# video_and_power.net
KiCad netlist of a schematic drawn in EAGLE
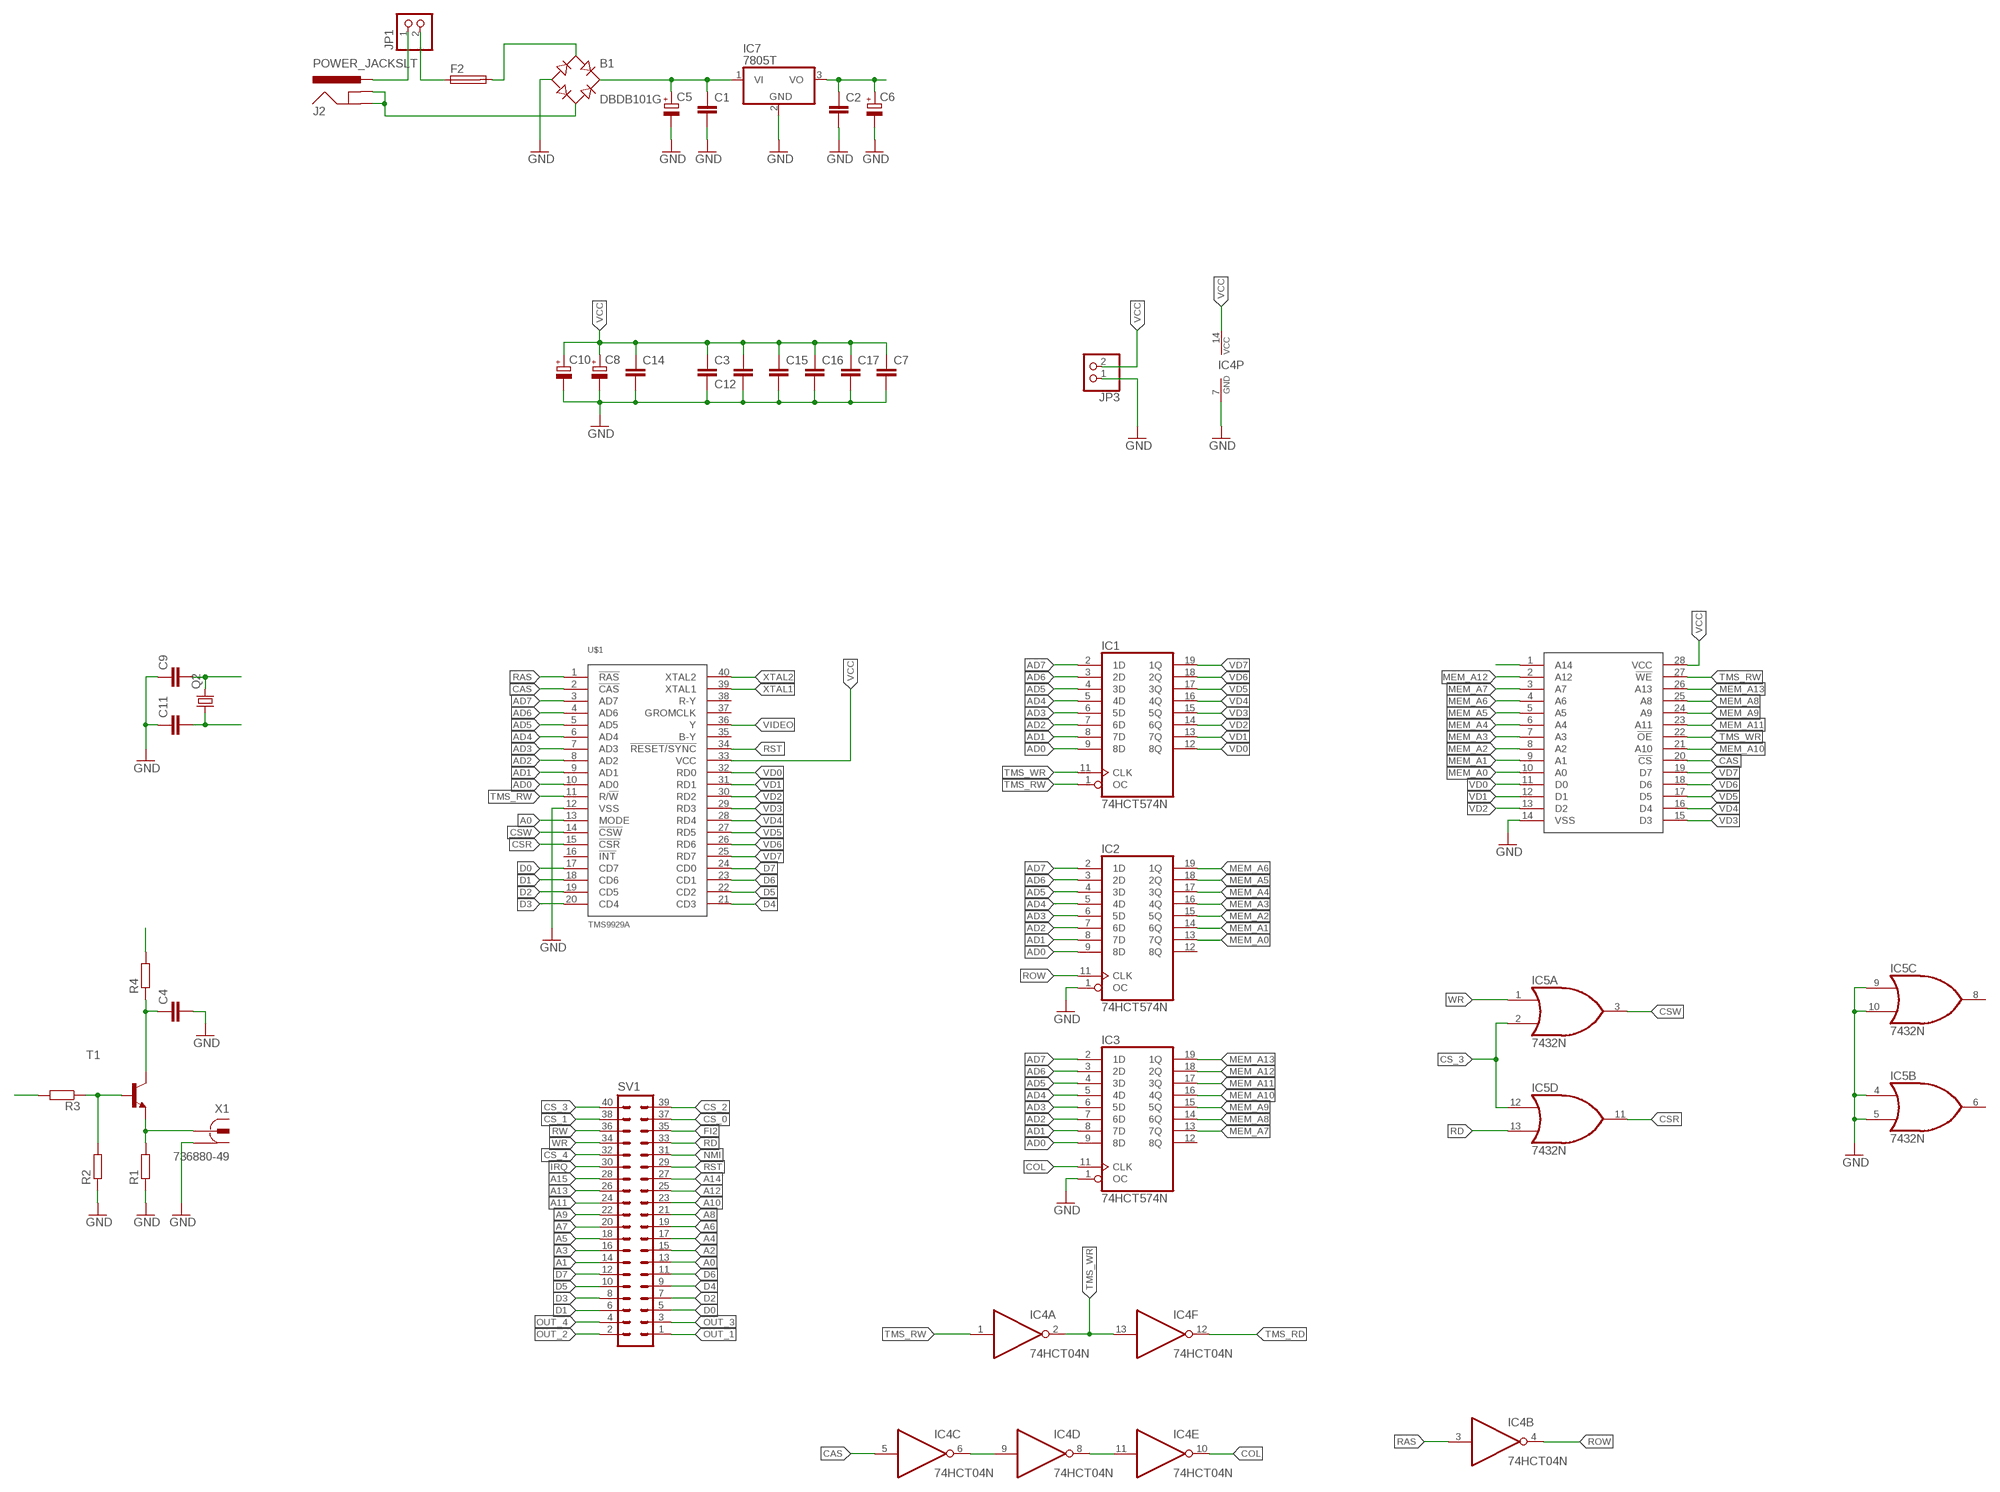
[diagram p0: schematic, sheet 1]

(export (version "E")
  (design (tool "Eeschema 10.0.6"))
  (components
    (comp (ref "B1")
      (value "DBDB101G")
      (footprint "eagle-import:DB")
      (libsource (lib "eagle-import") (part "DB?GDB101"))
    )
    (comp (ref "C1")
      (value "C-EUC1206")
      (footprint "eagle-import:C1206")
      (libsource (lib "eagle-import") (part "C-EUC1206"))
    )
    (comp (ref "C2")
      (value "C-EUC1206")
      (footprint "eagle-import:C1206")
      (libsource (lib "eagle-import") (part "C-EUC1206"))
    )
    (comp (ref "C3")
      (value "C-EUC0603")
      (footprint "eagle-import:C0603")
      (libsource (lib "eagle-import") (part "C-EUC0603"))
    )
    (comp (ref "C4")
      (value "C-EUC0603")
      (footprint "eagle-import:C0603")
      (libsource (lib "eagle-import") (part "C-EUC0603"))
    )
    (comp (ref "C5")
      (value "CPOL-EUE5-10.5")
      (footprint "eagle-import:E5-10,5")
      (libsource (lib "eagle-import") (part "CPOL-EUE5-10.5"))
    )
    (comp (ref "C6")
      (value "CPOL-EUE5-10.5")
      (footprint "eagle-import:E5-10,5")
      (libsource (lib "eagle-import") (part "CPOL-EUE5-10.5"))
    )
    (comp (ref "C7")
      (value "C-EUC1206")
      (footprint "eagle-import:C1206")
      (libsource (lib "eagle-import") (part "C-EUC1206"))
    )
    (comp (ref "C8")
      (value "CPOL-EUE5-10.5")
      (footprint "eagle-import:E5-10,5")
      (libsource (lib "eagle-import") (part "CPOL-EUE5-10.5"))
    )
    (comp (ref "C9")
      (value "C-EUC0603")
      (footprint "eagle-import:C0603")
      (libsource (lib "eagle-import") (part "C-EUC0603"))
    )
    (comp (ref "C10")
      (value "CPOL-EUE5-10.5")
      (footprint "eagle-import:E5-10,5")
      (libsource (lib "eagle-import") (part "CPOL-EUE5-10.5"))
    )
    (comp (ref "C11")
      (value "C-EUC0603")
      (footprint "eagle-import:C0603")
      (libsource (lib "eagle-import") (part "C-EUC0603"))
    )
    (comp (ref "C12")
      (value "C-EUC0603")
      (footprint "eagle-import:C0603")
      (libsource (lib "eagle-import") (part "C-EUC0603"))
    )
    (comp (ref "C14")
      (value "C-EUC1206")
      (footprint "eagle-import:C1206")
      (libsource (lib "eagle-import") (part "C-EUC1206"))
    )
    (comp (ref "C15")
      (value "C-EUC1206")
      (footprint "eagle-import:C1206")
      (libsource (lib "eagle-import") (part "C-EUC1206"))
    )
    (comp (ref "C16")
      (value "C-EUC0603")
      (footprint "eagle-import:C0603")
      (libsource (lib "eagle-import") (part "C-EUC0603"))
    )
    (comp (ref "C17")
      (value "C-EUC0603")
      (footprint "eagle-import:C0603")
      (libsource (lib "eagle-import") (part "C-EUC0603"))
    )
    (comp (ref "F2")
      (value "SH22,5")
      (footprint "eagle-import:SH22,5")
      (fields
        (field (name "MF") "SCHURTER")
        (field (name "MPN") "0031.8201")
        (field (name "MF_1") "SCHURTER")
        (field (name "MPN_1") "0031.8201")
        (field (name "OC_FARNELL") "1162740")
        (field (name "OC_NEWARK") "96F8317")
      )
      (libsource (lib "eagle-import") (part "SH22,5"))
    )
    (comp (ref "IC1")
      (value "74HCT574N")
      (footprint "eagle-import:DIL20")
      (libsource (lib "eagle-import") (part "74574NHCT"))
    )
    (comp (ref "IC2")
      (value "74HCT574N")
      (footprint "eagle-import:DIL20")
      (libsource (lib "eagle-import") (part "74574NHCT"))
    )
    (comp (ref "IC3")
      (value "74HCT574N")
      (footprint "eagle-import:DIL20")
      (libsource (lib "eagle-import") (part "74574NHCT"))
    )
    (comp (ref "IC4")
      (value "74HCT04N")
      (footprint "eagle-import:DIL14")
      (libsource (lib "eagle-import") (part "7404NHCT"))
    )
    (comp (ref "IC5")
      (value "7432N")
      (footprint "eagle-import:DIL14")
      (libsource (lib "eagle-import") (part "7432N"))
    )
    (comp (ref "IC7")
      (value "7805T")
      (footprint "eagle-import:TO220H")
      (libsource (lib "eagle-import") (part "78T05"))
    )
    (comp (ref "J2")
      (value "POWER_JACKSLT")
      (footprint "eagle-import:POWER_JACK_SLOT")
      (libsource (lib "eagle-import") (part "POWER_JACKSLT"))
    )
    (comp (ref "JP1")
      (value "PINHD-1X2")
      (footprint "eagle-import:1X02")
      (libsource (lib "eagle-import") (part "PINHD-1X2"))
    )
    (comp (ref "JP3")
      (value "PINHD-1X2/90")
      (footprint "eagle-import:1X02_90")
      (libsource (lib "eagle-import") (part "PINHD-1X2/90"))
    )
    (comp (ref "Q2")
      (value "CRYSTALHC49S")
      (footprint "eagle-import:HC49_S")
      (libsource (lib "eagle-import") (part "CRYSTALHC49S"))
    )
    (comp (ref "R1")
      (value "R-EU_R0603")
      (footprint "eagle-import:R0603")
      (libsource (lib "eagle-import") (part "R-EU_R0603"))
    )
    (comp (ref "R2")
      (value "R-EU_R0603")
      (footprint "eagle-import:R0603")
      (libsource (lib "eagle-import") (part "R-EU_R0603"))
    )
    (comp (ref "R3")
      (value "R-EU_0204/7")
      (footprint "eagle-import:0204_7")
      (libsource (lib "eagle-import") (part "R-EU_0204/7"))
    )
    (comp (ref "R4")
      (value "R-EU_R0805")
      (footprint "eagle-import:R0805")
      (libsource (lib "eagle-import") (part "R-EU_R0805"))
    )
    (comp (ref "SV1")
      (value "ML40L")
      (footprint "eagle-import:ML40L")
      (libsource (lib "eagle-import") (part "ML40L"))
    )
    (comp (ref "T1")
      (value "2N4401-NPN-TO92-EBC")
      (footprint "eagle-import:TO92-EBC")
      (libsource (lib "eagle-import") (part "-NPN-TO92-EBC2N4401"))
    )
    (comp (ref "U$1")
      (value "TMS9929A")
      (footprint "eagle-import:DIL40")
      (libsource (lib "eagle-import") (part "TMS9929A"))
    )
    (comp (ref "U$2")
      (value "62256")
      (footprint "eagle-import:DIL28-6")
      (libsource (lib "eagle-import") (part "62256"))
    )
    (comp (ref "X1")
      (value "736880-49")
      (footprint "eagle-import:736880-49")
      (libsource (lib "eagle-import") (part "736880-49"))
    )
  )
  (nets
    (net (code "1") (name "A0") (class "Default")
      (node (ref "SV1") (pin "13") (pinfunction "13_13") (pintype "passive"))
      (node (ref "U$1") (pin "13") (pinfunction "MODE_13") (pintype "bidirectional"))
    )
    (net (code "2") (name "A1") (class "Default")
      (node (ref "SV1") (pin "14") (pinfunction "14_14") (pintype "passive"))
    )
    (net (code "3") (name "A2") (class "Default")
      (node (ref "SV1") (pin "15") (pinfunction "15_15") (pintype "passive"))
    )
    (net (code "4") (name "A3") (class "Default")
      (node (ref "SV1") (pin "16") (pinfunction "16_16") (pintype "passive"))
    )
    (net (code "5") (name "A4") (class "Default")
      (node (ref "SV1") (pin "17") (pinfunction "17_17") (pintype "passive"))
    )
    (net (code "6") (name "A5") (class "Default")
      (node (ref "SV1") (pin "18") (pinfunction "18_18") (pintype "passive"))
    )
    (net (code "7") (name "A6") (class "Default")
      (node (ref "SV1") (pin "19") (pinfunction "19_19") (pintype "passive"))
    )
    (net (code "8") (name "A7") (class "Default")
      (node (ref "SV1") (pin "20") (pinfunction "20_20") (pintype "passive"))
    )
    (net (code "9") (name "A8") (class "Default")
      (node (ref "SV1") (pin "21") (pinfunction "21_21") (pintype "passive"))
    )
    (net (code "10") (name "A9") (class "Default")
      (node (ref "SV1") (pin "22") (pinfunction "22_22") (pintype "passive"))
    )
    (net (code "11") (name "A10") (class "Default")
      (node (ref "SV1") (pin "23") (pinfunction "23_23") (pintype "passive"))
    )
    (net (code "12") (name "A11") (class "Default")
      (node (ref "SV1") (pin "24") (pinfunction "24_24") (pintype "passive"))
    )
    (net (code "13") (name "A12") (class "Default")
      (node (ref "SV1") (pin "25") (pinfunction "25_25") (pintype "passive"))
    )
    (net (code "14") (name "A13") (class "Default")
      (node (ref "SV1") (pin "26") (pinfunction "26_26") (pintype "passive"))
    )
    (net (code "15") (name "A14") (class "Default")
      (node (ref "SV1") (pin "27") (pinfunction "27_27") (pintype "passive"))
    )
    (net (code "16") (name "A15") (class "Default")
      (node (ref "SV1") (pin "28") (pinfunction "28_28") (pintype "passive"))
    )
    (net (code "17") (name "AD0") (class "Default")
      (node (ref "IC1") (pin "9") (pinfunction "8D_9") (pintype "input"))
      (node (ref "IC2") (pin "9") (pinfunction "8D_9") (pintype "input"))
      (node (ref "IC3") (pin "9") (pinfunction "8D_9") (pintype "input"))
      (node (ref "U$1") (pin "10") (pinfunction "AD0_10") (pintype "bidirectional"))
    )
    (net (code "18") (name "AD1") (class "Default")
      (node (ref "IC1") (pin "8") (pinfunction "7D_8") (pintype "input"))
      (node (ref "IC2") (pin "8") (pinfunction "7D_8") (pintype "input"))
      (node (ref "IC3") (pin "8") (pinfunction "7D_8") (pintype "input"))
      (node (ref "U$1") (pin "9") (pinfunction "AD1_9") (pintype "bidirectional"))
    )
    (net (code "19") (name "AD2") (class "Default")
      (node (ref "IC1") (pin "7") (pinfunction "6D_7") (pintype "input"))
      (node (ref "IC2") (pin "7") (pinfunction "6D_7") (pintype "input"))
      (node (ref "IC3") (pin "7") (pinfunction "6D_7") (pintype "input"))
      (node (ref "U$1") (pin "8") (pinfunction "AD2_8") (pintype "bidirectional"))
    )
    (net (code "20") (name "AD3") (class "Default")
      (node (ref "IC1") (pin "6") (pinfunction "5D_6") (pintype "input"))
      (node (ref "IC2") (pin "6") (pinfunction "5D_6") (pintype "input"))
      (node (ref "IC3") (pin "6") (pinfunction "5D_6") (pintype "input"))
      (node (ref "U$1") (pin "7") (pinfunction "AD3_7") (pintype "bidirectional"))
    )
    (net (code "21") (name "AD4") (class "Default")
      (node (ref "IC1") (pin "5") (pinfunction "4D_5") (pintype "input"))
      (node (ref "IC2") (pin "5") (pinfunction "4D_5") (pintype "input"))
      (node (ref "IC3") (pin "5") (pinfunction "4D_5") (pintype "input"))
      (node (ref "U$1") (pin "6") (pinfunction "AD4_6") (pintype "bidirectional"))
    )
    (net (code "22") (name "AD5") (class "Default")
      (node (ref "IC1") (pin "4") (pinfunction "3D_4") (pintype "input"))
      (node (ref "IC2") (pin "4") (pinfunction "3D_4") (pintype "input"))
      (node (ref "IC3") (pin "4") (pinfunction "3D_4") (pintype "input"))
      (node (ref "U$1") (pin "5") (pinfunction "AD5_5") (pintype "bidirectional"))
    )
    (net (code "23") (name "AD6") (class "Default")
      (node (ref "IC1") (pin "3") (pinfunction "2D_3") (pintype "input"))
      (node (ref "IC2") (pin "3") (pinfunction "2D_3") (pintype "input"))
      (node (ref "IC3") (pin "3") (pinfunction "2D_3") (pintype "input"))
      (node (ref "U$1") (pin "4") (pinfunction "AD6_4") (pintype "bidirectional"))
    )
    (net (code "24") (name "AD7") (class "Default")
      (node (ref "IC1") (pin "2") (pinfunction "1D_2") (pintype "input"))
      (node (ref "IC2") (pin "2") (pinfunction "1D_2") (pintype "input"))
      (node (ref "IC3") (pin "2") (pinfunction "1D_2") (pintype "input"))
      (node (ref "U$1") (pin "3") (pinfunction "AD7_3") (pintype "bidirectional"))
    )
    (net (code "25") (name "CAS") (class "Default")
      (node (ref "IC4") (pin "5") (pinfunction "I_5") (pintype "input"))
      (node (ref "U$1") (pin "2") (pinfunction "~{CAS}_2") (pintype "bidirectional"))
      (node (ref "U$2") (pin "20") (pinfunction "~{CS}_20") (pintype "bidirectional"))
    )
    (net (code "26") (name "COL") (class "Default")
      (node (ref "IC3") (pin "11") (pinfunction "CLK_11") (pintype "input"))
      (node (ref "IC4") (pin "10") (pinfunction "O_10") (pintype "output"))
    )
    (net (code "27") (name "CSR") (class "Default")
      (node (ref "IC5") (pin "11") (pinfunction "O_11") (pintype "output"))
      (node (ref "U$1") (pin "15") (pinfunction "~{CSR}_15") (pintype "bidirectional"))
    )
    (net (code "28") (name "CSW") (class "Default")
      (node (ref "IC5") (pin "3") (pinfunction "O_3") (pintype "output"))
      (node (ref "U$1") (pin "14") (pinfunction "~{CSW}_14") (pintype "bidirectional"))
    )
    (net (code "29") (name "CS_0") (class "Default")
      (node (ref "SV1") (pin "37") (pinfunction "37_37") (pintype "passive"))
    )
    (net (code "30") (name "CS_1") (class "Default")
      (node (ref "SV1") (pin "38") (pinfunction "38_38") (pintype "passive"))
    )
    (net (code "31") (name "CS_2") (class "Default")
      (node (ref "SV1") (pin "39") (pinfunction "39_39") (pintype "passive"))
    )
    (net (code "32") (name "CS_3") (class "Default")
      (node (ref "IC5") (pin "12") (pinfunction "I0_12") (pintype "input"))
      (node (ref "IC5") (pin "2") (pinfunction "I1_2") (pintype "input"))
      (node (ref "SV1") (pin "40") (pinfunction "40_40") (pintype "passive"))
    )
    (net (code "33") (name "CS_4") (class "Default")
      (node (ref "SV1") (pin "32") (pinfunction "32_32") (pintype "passive"))
    )
    (net (code "34") (name "D0") (class "Default")
      (node (ref "SV1") (pin "5") (pinfunction "5_5") (pintype "passive"))
      (node (ref "U$1") (pin "17") (pinfunction "CD7_17") (pintype "bidirectional"))
    )
    (net (code "35") (name "D1") (class "Default")
      (node (ref "SV1") (pin "6") (pinfunction "6_6") (pintype "passive"))
      (node (ref "U$1") (pin "18") (pinfunction "CD6_18") (pintype "bidirectional"))
    )
    (net (code "36") (name "D2") (class "Default")
      (node (ref "SV1") (pin "7") (pinfunction "7_7") (pintype "passive"))
      (node (ref "U$1") (pin "19") (pinfunction "CD5_19") (pintype "bidirectional"))
    )
    (net (code "37") (name "D3") (class "Default")
      (node (ref "SV1") (pin "8") (pinfunction "8_8") (pintype "passive"))
      (node (ref "U$1") (pin "20") (pinfunction "CD4_20") (pintype "bidirectional"))
    )
    (net (code "38") (name "D4") (class "Default")
      (node (ref "SV1") (pin "9") (pinfunction "9_9") (pintype "passive"))
      (node (ref "U$1") (pin "21") (pinfunction "CD3_21") (pintype "bidirectional"))
    )
    (net (code "39") (name "D5") (class "Default")
      (node (ref "SV1") (pin "10") (pinfunction "10_10") (pintype "passive"))
      (node (ref "U$1") (pin "22") (pinfunction "CD2_22") (pintype "bidirectional"))
    )
    (net (code "40") (name "D6") (class "Default")
      (node (ref "SV1") (pin "11") (pinfunction "11_11") (pintype "passive"))
      (node (ref "U$1") (pin "23") (pinfunction "CD1_23") (pintype "bidirectional"))
    )
    (net (code "41") (name "D7") (class "Default")
      (node (ref "SV1") (pin "12") (pinfunction "12_12") (pintype "passive"))
      (node (ref "U$1") (pin "24") (pinfunction "CD0_24") (pintype "bidirectional"))
    )
    (net (code "42") (name "FI2") (class "Default")
      (node (ref "SV1") (pin "35") (pinfunction "35_35") (pintype "passive"))
    )
    (net (code "43") (name "GND") (class "Default")
      (node (ref "B1") (pin "-") (pinfunction "-_-") (pintype "passive"))
      (node (ref "C1") (pin "2") (pinfunction "2_2") (pintype "passive"))
      (node (ref "C10") (pin "-") (pinfunction "-_-") (pintype "passive"))
      (node (ref "C11") (pin "1") (pinfunction "1_1") (pintype "passive"))
      (node (ref "C12") (pin "1") (pinfunction "1_1") (pintype "passive"))
      (node (ref "C14") (pin "2") (pinfunction "2_2") (pintype "passive"))
      (node (ref "C15") (pin "2") (pinfunction "2_2") (pintype "passive"))
      (node (ref "C16") (pin "2") (pinfunction "2_2") (pintype "passive"))
      (node (ref "C17") (pin "2") (pinfunction "2_2") (pintype "passive"))
      (node (ref "C2") (pin "2") (pinfunction "2_2") (pintype "passive"))
      (node (ref "C3") (pin "2") (pinfunction "2_2") (pintype "passive"))
      (node (ref "C4") (pin "2") (pinfunction "2_2") (pintype "passive"))
      (node (ref "C5") (pin "-") (pinfunction "-_-") (pintype "passive"))
      (node (ref "C6") (pin "-") (pinfunction "-_-") (pintype "passive"))
      (node (ref "C7") (pin "2") (pinfunction "2_2") (pintype "passive"))
      (node (ref "C8") (pin "-") (pinfunction "-_-") (pintype "passive"))
      (node (ref "C9") (pin "1") (pinfunction "1_1") (pintype "passive"))
      (node (ref "IC2") (pin "1") (pinfunction "OC_1") (pintype "input"))
      (node (ref "IC3") (pin "1") (pinfunction "OC_1") (pintype "input"))
      (node (ref "IC4") (pin "7") (pinfunction "GND_7") (pintype "power_in"))
      (node (ref "IC5") (pin "10") (pinfunction "I1_10") (pintype "input"))
      (node (ref "IC5") (pin "4") (pinfunction "I0_4") (pintype "input"))
      (node (ref "IC5") (pin "5") (pinfunction "I1_5") (pintype "input"))
      (node (ref "IC5") (pin "9") (pinfunction "I0_9") (pintype "input"))
      (node (ref "IC7") (pin "2") (pinfunction "GND_2") (pintype "passive"))
      (node (ref "JP3") (pin "1") (pinfunction "1_1") (pintype "passive"))
      (node (ref "R1") (pin "1") (pinfunction "1_1") (pintype "passive"))
      (node (ref "R2") (pin "1") (pinfunction "1_1") (pintype "passive"))
      (node (ref "U$1") (pin "12") (pinfunction "VSS_12") (pintype "bidirectional"))
      (node (ref "U$2") (pin "14") (pinfunction "VSS_14") (pintype "bidirectional"))
      (node (ref "X1") (pin "1") (pinfunction "1_1") (pintype "passive"))
      (node (ref "X1") (pin "1@1") (pinfunction "1_1@1") (pintype "passive"))
      (node (ref "X1") (pin "1@2") (pinfunction "1_1@2") (pintype "passive"))
    )
    (net (code "44") (name "IRQ") (class "Default")
      (node (ref "SV1") (pin "30") (pinfunction "30_30") (pintype "passive"))
    )
    (net (code "45") (name "MEM_A0") (class "Default")
      (node (ref "IC2") (pin "13") (pinfunction "7Q_13") (pintype "tri_state"))
      (node (ref "U$2") (pin "10") (pinfunction "A0_10") (pintype "bidirectional"))
    )
    (net (code "46") (name "MEM_A1") (class "Default")
      (node (ref "IC2") (pin "14") (pinfunction "6Q_14") (pintype "tri_state"))
      (node (ref "U$2") (pin "9") (pinfunction "A1_9") (pintype "bidirectional"))
    )
    (net (code "47") (name "MEM_A2") (class "Default")
      (node (ref "IC2") (pin "15") (pinfunction "5Q_15") (pintype "tri_state"))
      (node (ref "U$2") (pin "8") (pinfunction "A2_8") (pintype "bidirectional"))
    )
    (net (code "48") (name "MEM_A3") (class "Default")
      (node (ref "IC2") (pin "16") (pinfunction "4Q_16") (pintype "tri_state"))
      (node (ref "U$2") (pin "7") (pinfunction "A3_7") (pintype "bidirectional"))
    )
    (net (code "49") (name "MEM_A4") (class "Default")
      (node (ref "IC2") (pin "17") (pinfunction "3Q_17") (pintype "tri_state"))
      (node (ref "U$2") (pin "6") (pinfunction "A4_6") (pintype "bidirectional"))
    )
    (net (code "50") (name "MEM_A5") (class "Default")
      (node (ref "IC2") (pin "18") (pinfunction "2Q_18") (pintype "tri_state"))
      (node (ref "U$2") (pin "5") (pinfunction "A5_5") (pintype "bidirectional"))
    )
    (net (code "51") (name "MEM_A6") (class "Default")
      (node (ref "IC2") (pin "19") (pinfunction "1Q_19") (pintype "tri_state"))
      (node (ref "U$2") (pin "4") (pinfunction "A6_4") (pintype "bidirectional"))
    )
    (net (code "52") (name "MEM_A7") (class "Default")
      (node (ref "IC3") (pin "13") (pinfunction "7Q_13") (pintype "tri_state"))
      (node (ref "U$2") (pin "3") (pinfunction "A7_3") (pintype "bidirectional"))
    )
    (net (code "53") (name "MEM_A8") (class "Default")
      (node (ref "IC3") (pin "14") (pinfunction "6Q_14") (pintype "tri_state"))
      (node (ref "U$2") (pin "25") (pinfunction "A8_25") (pintype "bidirectional"))
    )
    (net (code "54") (name "MEM_A9") (class "Default")
      (node (ref "IC3") (pin "15") (pinfunction "5Q_15") (pintype "tri_state"))
      (node (ref "U$2") (pin "24") (pinfunction "A9_24") (pintype "bidirectional"))
    )
    (net (code "55") (name "MEM_A10") (class "Default")
      (node (ref "IC3") (pin "16") (pinfunction "4Q_16") (pintype "tri_state"))
      (node (ref "U$2") (pin "21") (pinfunction "A10_21") (pintype "bidirectional"))
    )
    (net (code "56") (name "MEM_A11") (class "Default")
      (node (ref "IC3") (pin "17") (pinfunction "3Q_17") (pintype "tri_state"))
      (node (ref "U$2") (pin "23") (pinfunction "A11_23") (pintype "bidirectional"))
    )
    (net (code "57") (name "MEM_A12") (class "Default")
      (node (ref "IC3") (pin "18") (pinfunction "2Q_18") (pintype "tri_state"))
      (node (ref "U$2") (pin "2") (pinfunction "A12_2") (pintype "bidirectional"))
    )
    (net (code "58") (name "MEM_A13") (class "Default")
      (node (ref "IC3") (pin "19") (pinfunction "1Q_19") (pintype "tri_state"))
      (node (ref "U$2") (pin "26") (pinfunction "A13_26") (pintype "bidirectional"))
    )
    (net (code "59") (name "NMI") (class "Default")
      (node (ref "SV1") (pin "31") (pinfunction "31_31") (pintype "passive"))
    )
    (net (code "60") (name "Net-(B1-PadAC1)") (class "Default")
      (node (ref "B1") (pin "AC1") (pinfunction "AC1_AC1") (pintype "passive"))
      (node (ref "F2") (pin "2") (pinfunction "2_2") (pintype "passive"))
    )
    (net (code "61") (name "Net-(C4-Pad1)") (class "Default")
      (node (ref "C4") (pin "1") (pinfunction "1_1") (pintype "passive"))
      (node (ref "R4") (pin "1") (pinfunction "1_1") (pintype "passive"))
      (node (ref "T1") (pin "C") (pinfunction "C_C") (pintype "passive"))
    )
    (net (code "62") (name "Net-(F2-Pad1)") (class "Default")
      (node (ref "F2") (pin "1") (pinfunction "1_1") (pintype "passive"))
      (node (ref "JP1") (pin "2") (pinfunction "2_2") (pintype "passive"))
    )
    (net (code "63") (name "Net-(IC4C-O)") (class "Default")
      (node (ref "IC4") (pin "6") (pinfunction "O_6") (pintype "output"))
      (node (ref "IC4") (pin "9") (pinfunction "I_9") (pintype "input"))
    )
    (net (code "64") (name "Net-(IC4D-O)") (class "Default")
      (node (ref "IC4") (pin "11") (pinfunction "I_11") (pintype "input"))
      (node (ref "IC4") (pin "8") (pinfunction "O_8") (pintype "output"))
    )
    (net (code "65") (name "Net-(IC7-VI)") (class "Default")
      (node (ref "B1") (pin "+") (pinfunction "+_+") (pintype "passive"))
      (node (ref "C1") (pin "1") (pinfunction "1_1") (pintype "passive"))
      (node (ref "C5") (pin "+") (pinfunction "+_+") (pintype "passive"))
      (node (ref "IC7") (pin "1") (pinfunction "VI_1") (pintype "input"))
    )
    (net (code "66") (name "Net-(J2-GND)") (class "Default")
      (node (ref "B1") (pin "AC2") (pinfunction "AC2_AC2") (pintype "passive"))
      (node (ref "J2") (pin "GND@1") (pinfunction "GNDBREAK_GND@1") (pintype "bidirectional"))
      (node (ref "J2") (pin "GND@2") (pinfunction "GND_GND@2") (pintype "bidirectional"))
    )
    (net (code "67") (name "Net-(J2-PadPWR)") (class "Default")
      (node (ref "J2") (pin "PWR") (pinfunction "PWR_PWR") (pintype "bidirectional"))
      (node (ref "JP1") (pin "1") (pinfunction "1_1") (pintype "passive"))
    )
    (net (code "68") (name "Net-(R1-Pad2)") (class "Default")
      (node (ref "R1") (pin "2") (pinfunction "2_2") (pintype "passive"))
      (node (ref "T1") (pin "E") (pinfunction "E_E") (pintype "passive"))
      (node (ref "X1") (pin "2") (pinfunction "2_2") (pintype "passive"))
    )
    (net (code "69") (name "Net-(R2-Pad2)") (class "Default")
      (node (ref "R2") (pin "2") (pinfunction "2_2") (pintype "passive"))
      (node (ref "R3") (pin "1") (pinfunction "1_1") (pintype "passive"))
      (node (ref "T1") (pin "B") (pinfunction "B_B") (pintype "passive"))
    )
    (net (code "70") (name "OUT_1") (class "Default")
      (node (ref "SV1") (pin "1") (pinfunction "1_1") (pintype "passive"))
    )
    (net (code "71") (name "OUT_2") (class "Default")
      (node (ref "SV1") (pin "2") (pinfunction "2_2") (pintype "passive"))
    )
    (net (code "72") (name "OUT_3") (class "Default")
      (node (ref "SV1") (pin "3") (pinfunction "3_3") (pintype "passive"))
      (node (ref "U$2") (pin "1") (pinfunction "A14_1") (pintype "bidirectional"))
    )
    (net (code "73") (name "OUT_4") (class "Default")
      (node (ref "SV1") (pin "4") (pinfunction "4_4") (pintype "passive"))
    )
    (net (code "74") (name "RAS") (class "Default")
      (node (ref "IC4") (pin "3") (pinfunction "I_3") (pintype "input"))
      (node (ref "U$1") (pin "1") (pinfunction "~{RAS}_1") (pintype "bidirectional"))
    )
    (net (code "75") (name "RD") (class "Default")
      (node (ref "IC5") (pin "13") (pinfunction "I1_13") (pintype "input"))
      (node (ref "SV1") (pin "33") (pinfunction "33_33") (pintype "passive"))
    )
    (net (code "76") (name "ROW") (class "Default")
      (node (ref "IC2") (pin "11") (pinfunction "CLK_11") (pintype "input"))
      (node (ref "IC4") (pin "4") (pinfunction "O_4") (pintype "output"))
    )
    (net (code "77") (name "RST") (class "Default")
      (node (ref "SV1") (pin "29") (pinfunction "29_29") (pintype "passive"))
      (node (ref "U$1") (pin "34") (pinfunction "~{RESET/SYNC}_34") (pintype "bidirectional"))
    )
    (net (code "78") (name "RW") (class "Default")
      (node (ref "SV1") (pin "36") (pinfunction "36_36") (pintype "passive"))
    )
    (net (code "79") (name "TMS_RD") (class "Default")
      (node (ref "IC4") (pin "12") (pinfunction "O_12") (pintype "output"))
    )
    (net (code "80") (name "TMS_RW") (class "Default")
      (node (ref "IC1") (pin "1") (pinfunction "OC_1") (pintype "input"))
      (node (ref "IC4") (pin "1") (pinfunction "I_1") (pintype "input"))
      (node (ref "U$1") (pin "11") (pinfunction "R/~{W}_11") (pintype "bidirectional"))
      (node (ref "U$2") (pin "27") (pinfunction "~{WE}_27") (pintype "bidirectional"))
    )
    (net (code "81") (name "TMS_WR") (class "Default")
      (node (ref "IC1") (pin "11") (pinfunction "CLK_11") (pintype "input"))
      (node (ref "IC4") (pin "13") (pinfunction "I_13") (pintype "input"))
      (node (ref "IC4") (pin "2") (pinfunction "O_2") (pintype "output"))
      (node (ref "U$2") (pin "22") (pinfunction "~{OE}_22") (pintype "bidirectional"))
    )
    (net (code "82") (name "VCC") (class "Default")
      (node (ref "C10") (pin "+") (pinfunction "+_+") (pintype "passive"))
      (node (ref "C12") (pin "2") (pinfunction "2_2") (pintype "passive"))
      (node (ref "C14") (pin "1") (pinfunction "1_1") (pintype "passive"))
      (node (ref "C15") (pin "1") (pinfunction "1_1") (pintype "passive"))
      (node (ref "C16") (pin "1") (pinfunction "1_1") (pintype "passive"))
      (node (ref "C17") (pin "1") (pinfunction "1_1") (pintype "passive"))
      (node (ref "C2") (pin "1") (pinfunction "1_1") (pintype "passive"))
      (node (ref "C3") (pin "1") (pinfunction "1_1") (pintype "passive"))
      (node (ref "C6") (pin "+") (pinfunction "+_+") (pintype "passive"))
      (node (ref "C7") (pin "1") (pinfunction "1_1") (pintype "passive"))
      (node (ref "C8") (pin "+") (pinfunction "+_+") (pintype "passive"))
      (node (ref "IC4") (pin "14") (pinfunction "VCC_14") (pintype "power_in"))
      (node (ref "IC7") (pin "3") (pinfunction "VO_3") (pintype "passive"))
      (node (ref "JP3") (pin "2") (pinfunction "2_2") (pintype "passive"))
      (node (ref "R4") (pin "2") (pinfunction "2_2") (pintype "passive"))
      (node (ref "U$1") (pin "33") (pinfunction "VCC_33") (pintype "bidirectional"))
      (node (ref "U$2") (pin "28") (pinfunction "VCC_28") (pintype "bidirectional"))
    )
    (net (code "83") (name "VD0") (class "Default")
      (node (ref "IC1") (pin "12") (pinfunction "8Q_12") (pintype "tri_state"))
      (node (ref "U$1") (pin "32") (pinfunction "RD0_32") (pintype "bidirectional"))
      (node (ref "U$2") (pin "11") (pinfunction "D0_11") (pintype "bidirectional"))
    )
    (net (code "84") (name "VD1") (class "Default")
      (node (ref "IC1") (pin "13") (pinfunction "7Q_13") (pintype "tri_state"))
      (node (ref "U$1") (pin "31") (pinfunction "RD1_31") (pintype "bidirectional"))
      (node (ref "U$2") (pin "12") (pinfunction "D1_12") (pintype "bidirectional"))
    )
    (net (code "85") (name "VD2") (class "Default")
      (node (ref "IC1") (pin "14") (pinfunction "6Q_14") (pintype "tri_state"))
      (node (ref "U$1") (pin "30") (pinfunction "RD2_30") (pintype "bidirectional"))
      (node (ref "U$2") (pin "13") (pinfunction "D2_13") (pintype "bidirectional"))
    )
    (net (code "86") (name "VD3") (class "Default")
      (node (ref "IC1") (pin "15") (pinfunction "5Q_15") (pintype "tri_state"))
      (node (ref "U$1") (pin "29") (pinfunction "RD3_29") (pintype "bidirectional"))
      (node (ref "U$2") (pin "15") (pinfunction "D3_15") (pintype "bidirectional"))
    )
    (net (code "87") (name "VD4") (class "Default")
      (node (ref "IC1") (pin "16") (pinfunction "4Q_16") (pintype "tri_state"))
      (node (ref "U$1") (pin "28") (pinfunction "RD4_28") (pintype "bidirectional"))
      (node (ref "U$2") (pin "16") (pinfunction "D4_16") (pintype "bidirectional"))
    )
    (net (code "88") (name "VD5") (class "Default")
      (node (ref "IC1") (pin "17") (pinfunction "3Q_17") (pintype "tri_state"))
      (node (ref "U$1") (pin "27") (pinfunction "RD5_27") (pintype "bidirectional"))
      (node (ref "U$2") (pin "17") (pinfunction "D5_17") (pintype "bidirectional"))
    )
    (net (code "89") (name "VD6") (class "Default")
      (node (ref "IC1") (pin "18") (pinfunction "2Q_18") (pintype "tri_state"))
      (node (ref "U$1") (pin "26") (pinfunction "RD6_26") (pintype "bidirectional"))
      (node (ref "U$2") (pin "18") (pinfunction "D6_18") (pintype "bidirectional"))
    )
    (net (code "90") (name "VD7") (class "Default")
      (node (ref "IC1") (pin "19") (pinfunction "1Q_19") (pintype "tri_state"))
      (node (ref "U$1") (pin "25") (pinfunction "RD7_25") (pintype "bidirectional"))
      (node (ref "U$2") (pin "19") (pinfunction "D7_19") (pintype "bidirectional"))
    )
    (net (code "91") (name "VIDEO") (class "Default")
      (node (ref "R3") (pin "2") (pinfunction "2_2") (pintype "passive"))
      (node (ref "U$1") (pin "36") (pinfunction "Y_36") (pintype "bidirectional"))
    )
    (net (code "92") (name "WR") (class "Default")
      (node (ref "IC5") (pin "1") (pinfunction "I0_1") (pintype "input"))
      (node (ref "SV1") (pin "34") (pinfunction "34_34") (pintype "passive"))
    )
    (net (code "93") (name "XTAL1") (class "Default")
      (node (ref "C9") (pin "2") (pinfunction "2_2") (pintype "passive"))
      (node (ref "Q2") (pin "2") (pinfunction "2_2") (pintype "passive"))
      (node (ref "U$1") (pin "39") (pinfunction "XTAL1_39") (pintype "bidirectional"))
    )
    (net (code "94") (name "XTAL2") (class "Default")
      (node (ref "C11") (pin "2") (pinfunction "2_2") (pintype "passive"))
      (node (ref "Q2") (pin "1") (pinfunction "1_1") (pintype "passive"))
      (node (ref "U$1") (pin "40") (pinfunction "XTAL2_40") (pintype "bidirectional"))
    )
    (net (code "95") (name "unconnected-(IC2A-8Q-Pad12)") (class "Default")
      (node (ref "IC2") (pin "12") (pinfunction "8Q_12") (pintype "tri_state"))
    )
    (net (code "96") (name "unconnected-(IC3A-8Q-Pad12)") (class "Default")
      (node (ref "IC3") (pin "12") (pinfunction "8Q_12") (pintype "tri_state"))
    )
    (net (code "97") (name "unconnected-(IC5B-O-Pad6)") (class "Default")
      (node (ref "IC5") (pin "6") (pinfunction "O_6") (pintype "output"))
    )
    (net (code "98") (name "unconnected-(IC5C-O-Pad8)") (class "Default")
      (node (ref "IC5") (pin "8") (pinfunction "O_8") (pintype "output"))
    )
    (net (code "99") (name "unconnected-(U$1-B-Y-Pad35)") (class "Default")
      (node (ref "U$1") (pin "35") (pinfunction "B-Y_35") (pintype "bidirectional"))
    )
    (net (code "100") (name "unconnected-(U$1-GROMCLK-Pad37)") (class "Default")
      (node (ref "U$1") (pin "37") (pinfunction "GROMCLK_37") (pintype "bidirectional"))
    )
    (net (code "101") (name "unconnected-(U$1-R-Y-Pad38)") (class "Default")
      (node (ref "U$1") (pin "38") (pinfunction "R-Y_38") (pintype "bidirectional"))
    )
    (net (code "102") (name "unconnected-(U$1-~{INT}-Pad16)") (class "Default")
      (node (ref "U$1") (pin "16") (pinfunction "~{INT}_16") (pintype "bidirectional"))
    )
  )
)
